# 0_Overview.net
KiCad netlist of a schematic drawn in Altium Designer
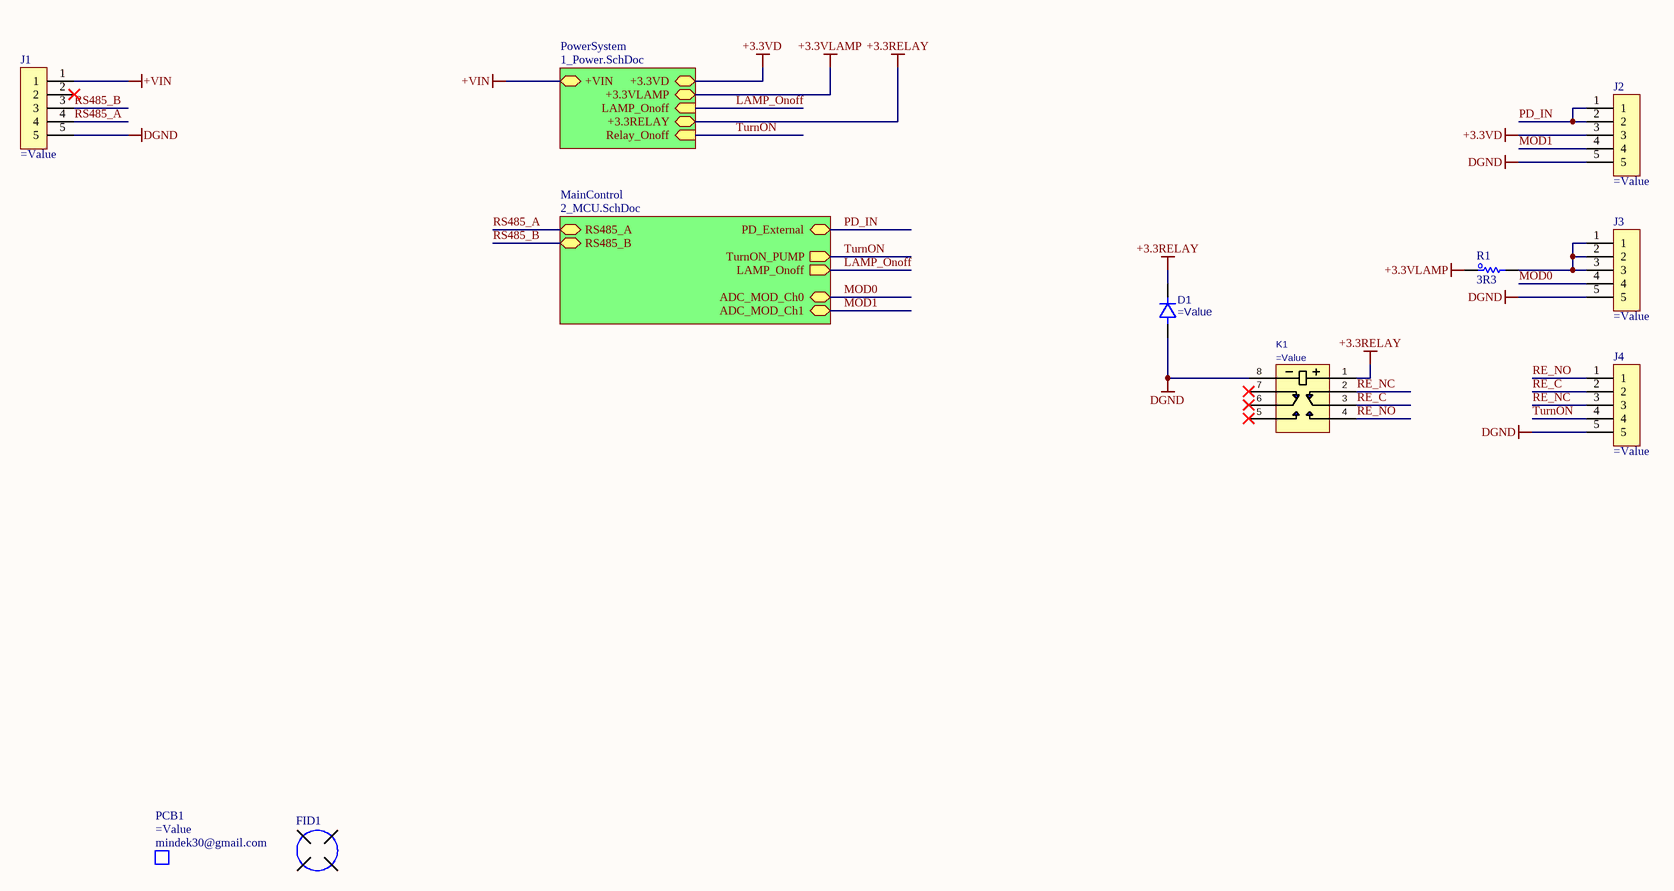
[diagram p0: 0_Overview.SchDoc]

(export (version "E")
  (design (tool "Eeschema 10.0.6"))
  (components
    (comp (ref "D1")
      (value "~")
      (footprint "SOD323")
      (description "DIODE SCHOTTKY 40V 2A 0603")
      (fields (field (name "MANUFACTURER") "Slkor(SLKORMICRO Elec.)") (field (name "PARTNUMBER") "SD103AWS"))
      (libsource (lib "UUSymbol") (part "D_PW_SD103AWS"))
    )
    (comp (ref "FID1")
      (value "FIDUCIAL")
      (footprint "FID")
      (description "Fiducial")
      (fields (field (name "MANUFACTURER") "mindek30@gmail.com") (field (name "PARTNUMBER") "_"))
      (libsource (lib "UUSymbol") (part "FID_FIDUCIAL"))
    )
    (comp (ref "J1")
      (value "~")
      (footprint "MOLEX_532610571")
      (description "CONN HEADER SMD R/A 5POS 1.25MM")
      (fields (field (name "PARTNUMBER") "0532610571") (field (name "MANUFACTURER") "Molex"))
      (libsource (lib "UUSymbol") (part "CON_5P_532610571"))
    )
    (comp (ref "J2")
      (value "~")
      (footprint "MOLEX_532610571")
      (description "CONN HEADER SMD R/A 5POS 1.25MM")
      (fields (field (name "PARTNUMBER") "0532610571") (field (name "MANUFACTURER") "Molex"))
      (libsource (lib "") (part "CON_5P_532610571_1"))
    )
    (comp (ref "J3")
      (value "~")
      (footprint "MOLEX_532610571")
      (description "CONN HEADER SMD R/A 5POS 1.25MM")
      (fields (field (name "PARTNUMBER") "0532610571") (field (name "MANUFACTURER") "Molex"))
      (libsource (lib "") (part "CON_5P_532610571_1"))
    )
    (comp (ref "J4")
      (value "~")
      (footprint "MOLEX_532610571")
      (description "CONN HEADER SMD R/A 5POS 1.25MM")
      (fields (field (name "PARTNUMBER") "0532610571") (field (name "MANUFACTURER") "Molex"))
      (libsource (lib "") (part "CON_5P_532610571_1"))
    )
    (comp (ref "K1")
      (value "~")
      (footprint "RELAY_HFD4/12-SR")
      (description "Telecom Non Latching 3VDC DPDT SMD Relays RoHS")
      (fields
        (field (name "MANUFACTURER") "Xiamen Hongfa Electroacoustic")
        (field (name "PARTNUMBER") "HFD4/3-S1R")
      )
      (libsource (lib "UUSymbol") (part "SW_RELAY_HFD4/12-SR"))
    )
    (comp (ref "PCB1")
      (value "~")
      (description "BARE PCB")
      (fields (field (name "MANUFACTURER") "mindek30@gmail.com") (field (name "PARTNUMBER") "_"))
      (libsource (lib "UUSymbol") (part "PCB_Bare"))
    )
    (comp (ref "R1")
      (value "3R3")
      (footprint "R_2512")
      (description "RES SMD 3.3 OHM 5% 3W 2512")
      (fields (field (name "MANUFACTURER") "Vishay") (field (name "PARTNUMBER") "35223R3JT"))
      (libsource (lib "UUSymbol") (part "R_Resister"))
    )
  )
  (nets
    (net (code "1") (name "+3.3RELAY") (class "Default")
      (node (ref "D1") (pin "1") (pinfunction "1_1") (pintype "passive"))
      (node (ref "K1") (pin "1") (pinfunction "1_1") (pintype "passive"))
    )
    (net (code "2") (name "+3.3VD") (class "Default")
      (node (ref "J2") (pin "3") (pinfunction "3_3") (pintype "passive"))
    )
    (net (code "3") (name "+3.3VLAMP") (class "Default")
      (node (ref "R1") (pin "1") (pinfunction "1_1") (pintype "passive"))
    )
    (net (code "4") (name "+VIN") (class "Default")
      (node (ref "J1") (pin "1") (pinfunction "1_1") (pintype "passive"))
    )
    (net (code "6") (name "/MOD0") (class "Default")
      (node (ref "J3") (pin "4") (pinfunction "4_4") (pintype "passive"))
    )
    (net (code "7") (name "/MOD1") (class "Default")
      (node (ref "J2") (pin "4") (pinfunction "4_4") (pintype "passive"))
    )
    (net (code "8") (name "/PD_IN") (class "Default")
      (node (ref "J2") (pin "1") (pinfunction "1_1") (pintype "passive"))
      (node (ref "J2") (pin "2") (pinfunction "2_2") (pintype "passive"))
    )
    (net (code "9") (name "/RE_C") (class "Default")
      (node (ref "J4") (pin "2") (pinfunction "2_2") (pintype "passive"))
      (node (ref "K1") (pin "3") (pinfunction "3_3") (pintype "passive"))
    )
    (net (code "10") (name "/RE_NC") (class "Default")
      (node (ref "J4") (pin "3") (pinfunction "3_3") (pintype "passive"))
      (node (ref "K1") (pin "2") (pinfunction "2_2") (pintype "passive"))
    )
    (net (code "11") (name "/RE_NO") (class "Default")
      (node (ref "J4") (pin "1") (pinfunction "1_1") (pintype "passive"))
      (node (ref "K1") (pin "4") (pinfunction "4_4") (pintype "passive"))
    )
    (net (code "12") (name "/RS485_A") (class "Default")
      (node (ref "J1") (pin "4") (pinfunction "4_4") (pintype "passive"))
    )
    (net (code "13") (name "/RS485_B") (class "Default")
      (node (ref "J1") (pin "3") (pinfunction "3_3") (pintype "passive"))
    )
    (net (code "14") (name "/TurnON") (class "Default")
      (node (ref "J4") (pin "4") (pinfunction "4_4") (pintype "passive"))
    )
    (net (code "15") (name "DGND") (class "Default")
      (node (ref "D1") (pin "2") (pinfunction "2_2") (pintype "passive"))
      (node (ref "J1") (pin "5") (pinfunction "5_5") (pintype "passive"))
      (node (ref "J2") (pin "5") (pinfunction "5_5") (pintype "passive"))
      (node (ref "J3") (pin "5") (pinfunction "5_5") (pintype "passive"))
      (node (ref "J4") (pin "5") (pinfunction "5_5") (pintype "passive"))
      (node (ref "K1") (pin "8") (pinfunction "8_8") (pintype "passive"))
    )
    (net (code "16") (name "Net-(J3-Pad1)") (class "Default")
      (node (ref "J3") (pin "1") (pinfunction "1_1") (pintype "passive"))
      (node (ref "J3") (pin "2") (pinfunction "2_2") (pintype "passive"))
      (node (ref "J3") (pin "3") (pinfunction "3_3") (pintype "passive"))
      (node (ref "R1") (pin "2") (pinfunction "2_2") (pintype "passive"))
    )
    (net (code "17") (name "unconnected-(J1-Pad2)") (class "Default")
      (node (ref "J1") (pin "2") (pinfunction "2_2") (pintype "passive+no_connect"))
    )
    (net (code "18") (name "unconnected-(K1-Pad5)") (class "Default")
      (node (ref "K1") (pin "5") (pinfunction "5_5") (pintype "passive+no_connect"))
    )
    (net (code "19") (name "unconnected-(K1-Pad6)") (class "Default")
      (node (ref "K1") (pin "6") (pinfunction "6_6") (pintype "passive+no_connect"))
    )
    (net (code "20") (name "unconnected-(K1-Pad7)") (class "Default")
      (node (ref "K1") (pin "7") (pinfunction "7_7") (pintype "passive+no_connect"))
    )
  )
)
